# 04_STORAGE.net
KiCad netlist of a schematic drawn in Altium Designer
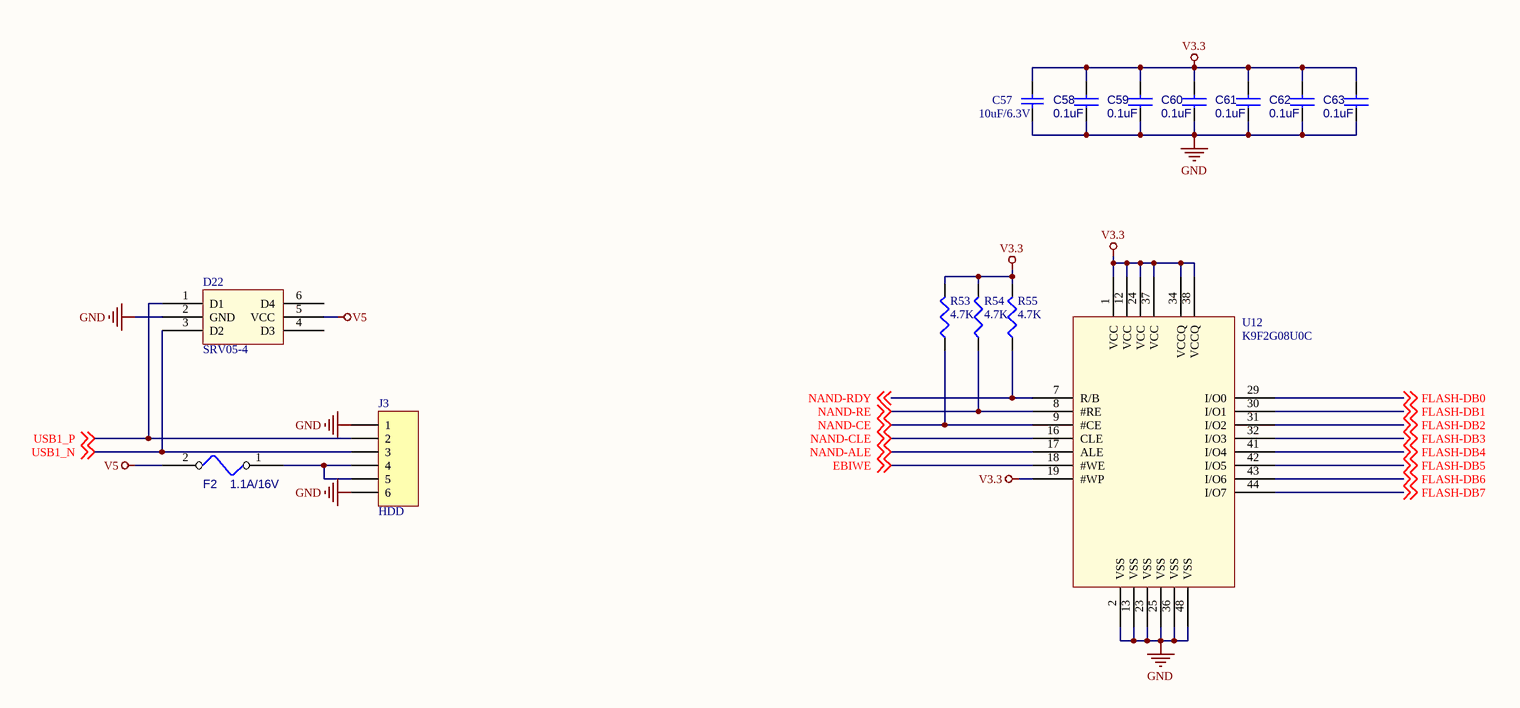
[diagram p0: [04]STORAGE.SchDoc]

(export (version "E")
  (design (tool "Eeschema 10.0.6"))
  (components
    (comp (ref "C57")
      (value "10uF/6.3V")
      (footprint "0805")
      (description "Capacitor")
      (libsource (lib "Miscellaneous Devices") (part "Cap"))
    )
    (comp (ref "C58") (value "0.1uF") (footprint "0603") (libsource (lib "*") (part "CAP NP_Dup2")))
    (comp (ref "C59") (value "0.1uF") (footprint "0603") (libsource (lib "*") (part "CAP NP_Dup2")))
    (comp (ref "C60") (value "0.1uF") (footprint "0603") (libsource (lib "*") (part "CAP NP_Dup2")))
    (comp (ref "C61") (value "0.1uF") (footprint "0603") (libsource (lib "*") (part "CAP NP_Dup2")))
    (comp (ref "C62") (value "0.1uF") (footprint "0603") (libsource (lib "*") (part "CAP NP_Dup2")))
    (comp (ref "C63") (value "0.1uF") (footprint "0603") (libsource (lib "*") (part "CAP NP_Dup2")))
    (comp (ref "D22") (value "SRV05-4") (footprint "SOT23-6") (libsource (lib "Schlib") (part "SRV05-4")))
    (comp (ref "F2") (value "1.1A/16V") (libsource (lib "*") (part "2A_32VDC_0467-002")))
    (comp (ref "J3")
      (value "HDD")
      (footprint "HDD-CONN")
      (description "Header, 6-Pin")
      (fields (field (name "PUBLISHER") "Altium Limited"))
      (libsource (lib "Miscellaneous Connectors") (part "Header 6"))
    )
    (comp (ref "R53")
      (value "4.7K")
      (footprint "0603")
      (description "Resistor")
      (libsource (lib "Miscellaneous Devices") (part "Res3"))
    )
    (comp (ref "R54")
      (value "4.7K")
      (footprint "0603")
      (description "Resistor")
      (libsource (lib "Miscellaneous Devices") (part "Res3"))
    )
    (comp (ref "R55")
      (value "4.7K")
      (footprint "0603")
      (description "Resistor")
      (libsource (lib "Miscellaneous Devices") (part "Res3"))
    )
    (comp (ref "U12")
      (value "K9F2G08U0C")
      (footprint "TSOP48")
      (libsource (lib "Schlib") (part "K9GBG08U0A"))
    )
  )
  (nets
    (net (code "1") (name "EBIWE") (class "Default")
      (node (ref "U12") (pin "18") (pinfunction "#WE_18") (pintype "passive"))
    )
    (net (code "2") (name "FLASH-DB0") (class "Default")
      (node (ref "U12") (pin "29") (pinfunction "I/O0_29") (pintype "passive"))
    )
    (net (code "3") (name "FLASH-DB1") (class "Default")
      (node (ref "U12") (pin "30") (pinfunction "I/O1_30") (pintype "passive"))
    )
    (net (code "4") (name "FLASH-DB2") (class "Default")
      (node (ref "U12") (pin "31") (pinfunction "I/O2_31") (pintype "passive"))
    )
    (net (code "5") (name "FLASH-DB3") (class "Default")
      (node (ref "U12") (pin "32") (pinfunction "I/O3_32") (pintype "passive"))
    )
    (net (code "6") (name "FLASH-DB4") (class "Default")
      (node (ref "U12") (pin "41") (pinfunction "I/O4_41") (pintype "passive"))
    )
    (net (code "7") (name "FLASH-DB5") (class "Default")
      (node (ref "U12") (pin "42") (pinfunction "I/O5_42") (pintype "passive"))
    )
    (net (code "8") (name "FLASH-DB6") (class "Default")
      (node (ref "U12") (pin "43") (pinfunction "I/O6_43") (pintype "passive"))
    )
    (net (code "9") (name "FLASH-DB7") (class "Default")
      (node (ref "U12") (pin "44") (pinfunction "I/O7_44") (pintype "passive"))
    )
    (net (code "10") (name "GND") (class "Default")
      (node (ref "C57") (pin "1") (pinfunction "1_1") (pintype "passive"))
      (node (ref "C58") (pin "1") (pinfunction "1_1") (pintype "passive"))
      (node (ref "C59") (pin "1") (pinfunction "1_1") (pintype "passive"))
      (node (ref "C60") (pin "1") (pinfunction "1_1") (pintype "passive"))
      (node (ref "C61") (pin "1") (pinfunction "1_1") (pintype "passive"))
      (node (ref "C62") (pin "1") (pinfunction "1_1") (pintype "passive"))
      (node (ref "C63") (pin "1") (pinfunction "1_1") (pintype "passive"))
      (node (ref "D22") (pin "2") (pinfunction "GND_2") (pintype "passive"))
      (node (ref "J3") (pin "1") (pinfunction "1_1") (pintype "passive"))
      (node (ref "J3") (pin "6") (pinfunction "6_6") (pintype "passive"))
      (node (ref "U12") (pin "13") (pinfunction "VSS_13") (pintype "passive"))
      (node (ref "U12") (pin "2") (pinfunction "VSS_2") (pintype "passive"))
      (node (ref "U12") (pin "23") (pinfunction "VSS_23") (pintype "passive"))
      (node (ref "U12") (pin "25") (pinfunction "VSS_25") (pintype "passive"))
      (node (ref "U12") (pin "36") (pinfunction "VSS_36") (pintype "passive"))
      (node (ref "U12") (pin "48") (pinfunction "VSS_48") (pintype "passive"))
    )
    (net (code "11") (name "NAND-ALE") (class "Default")
      (node (ref "U12") (pin "17") (pinfunction "ALE_17") (pintype "passive"))
    )
    (net (code "12") (name "NAND-CE") (class "Default")
      (node (ref "R53") (pin "1") (pinfunction "1_1") (pintype "passive"))
      (node (ref "U12") (pin "9") (pinfunction "#CE_9") (pintype "passive"))
    )
    (net (code "13") (name "NAND-CLE") (class "Default")
      (node (ref "U12") (pin "16") (pinfunction "CLE_16") (pintype "passive"))
    )
    (net (code "14") (name "NAND-RDY") (class "Default")
      (node (ref "R55") (pin "1") (pinfunction "1_1") (pintype "passive"))
      (node (ref "U12") (pin "7") (pinfunction "R/B_7") (pintype "passive"))
    )
    (net (code "15") (name "NAND-RE") (class "Default")
      (node (ref "R54") (pin "1") (pinfunction "1_1") (pintype "passive"))
      (node (ref "U12") (pin "8") (pinfunction "#RE_8") (pintype "passive"))
    )
    (net (code "16") (name "Net-(F2-Pad1)") (class "Default")
      (node (ref "F2") (pin "1") (pinfunction "1_1") (pintype "passive"))
      (node (ref "J3") (pin "4") (pinfunction "4_4") (pintype "passive"))
      (node (ref "J3") (pin "5") (pinfunction "5_5") (pintype "passive"))
    )
    (net (code "17") (name "USB1_N") (class "Default")
      (node (ref "D22") (pin "3") (pinfunction "D2_3") (pintype "passive"))
      (node (ref "J3") (pin "3") (pinfunction "3_3") (pintype "passive"))
    )
    (net (code "18") (name "USB1_P") (class "Default")
      (node (ref "D22") (pin "1") (pinfunction "D1_1") (pintype "passive"))
      (node (ref "J3") (pin "2") (pinfunction "2_2") (pintype "passive"))
    )
    (net (code "19") (name "V3.3") (class "Default")
      (node (ref "C57") (pin "2") (pinfunction "2_2") (pintype "passive"))
      (node (ref "C58") (pin "2") (pinfunction "2_2") (pintype "passive"))
      (node (ref "C59") (pin "2") (pinfunction "2_2") (pintype "passive"))
      (node (ref "C60") (pin "2") (pinfunction "2_2") (pintype "passive"))
      (node (ref "C61") (pin "2") (pinfunction "2_2") (pintype "passive"))
      (node (ref "C62") (pin "2") (pinfunction "2_2") (pintype "passive"))
      (node (ref "C63") (pin "2") (pinfunction "2_2") (pintype "passive"))
      (node (ref "R53") (pin "2") (pinfunction "2_2") (pintype "passive"))
      (node (ref "R54") (pin "2") (pinfunction "2_2") (pintype "passive"))
      (node (ref "R55") (pin "2") (pinfunction "2_2") (pintype "passive"))
      (node (ref "U12") (pin "1") (pinfunction "VCC_1") (pintype "passive"))
      (node (ref "U12") (pin "12") (pinfunction "VCC_12") (pintype "passive"))
      (node (ref "U12") (pin "19") (pinfunction "#WP_19") (pintype "passive"))
      (node (ref "U12") (pin "24") (pinfunction "VCC_24") (pintype "passive"))
      (node (ref "U12") (pin "34") (pinfunction "VCCQ_34") (pintype "passive"))
      (node (ref "U12") (pin "37") (pinfunction "VCC_37") (pintype "passive"))
      (node (ref "U12") (pin "38") (pinfunction "VCCQ_38") (pintype "passive"))
    )
    (net (code "20") (name "V5") (class "Default")
      (node (ref "D22") (pin "5") (pinfunction "VCC_5") (pintype "passive"))
      (node (ref "F2") (pin "2") (pinfunction "2_2") (pintype "passive"))
    )
    (net (code "21") (name "unconnected-(D22-D3-Pad4)") (class "Default")
      (node (ref "D22") (pin "4") (pinfunction "D3_4") (pintype "passive"))
    )
    (net (code "22") (name "unconnected-(D22-D4-Pad6)") (class "Default")
      (node (ref "D22") (pin "6") (pinfunction "D4_6") (pintype "passive"))
    )
  )
)
